# PSPS_AVNC_MITCH_2021-0_PRODUCTION.net
KiCad netlist of a schematic drawn in EAGLE
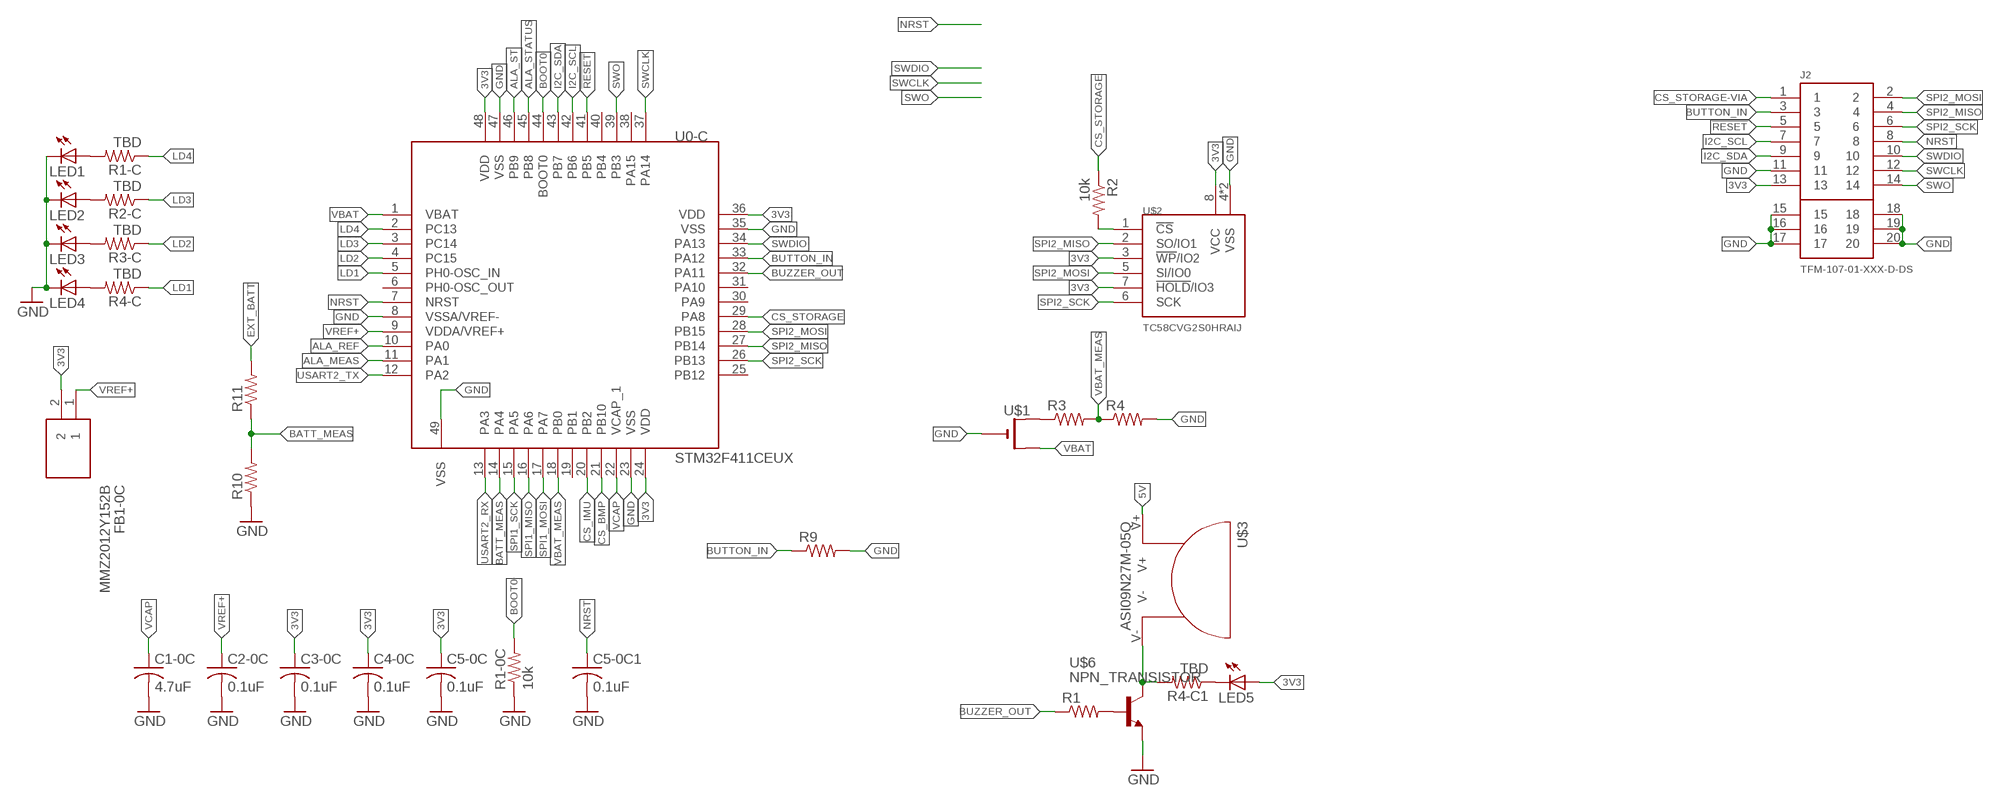
[diagram p0: schematic, sheet 1]
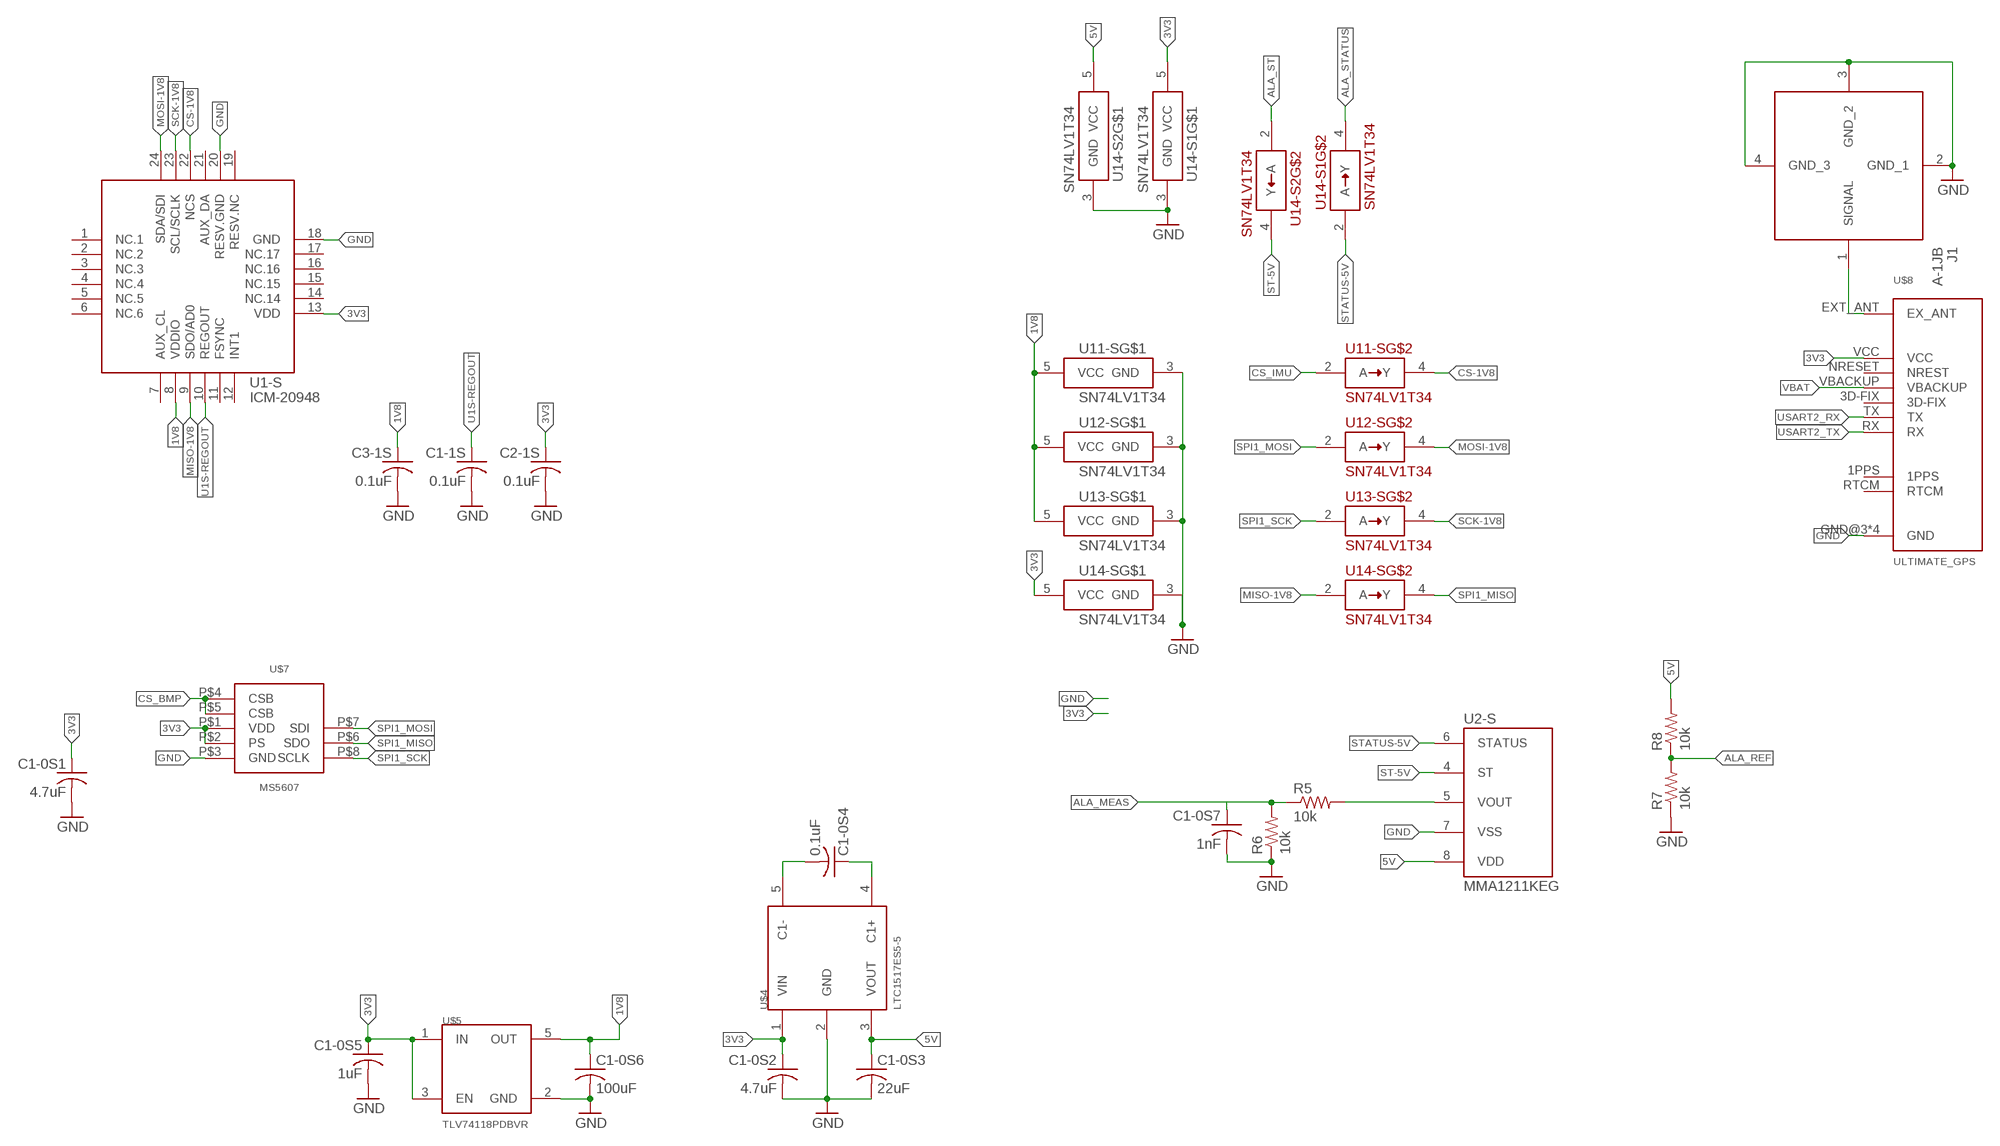
[diagram p1: schematic, sheet 2]

(export (version "E")
  (design (tool "Eeschema 10.0.6"))
  (components
    (comp (ref "C1-0C")
      (value "4.7uF")
      (footprint "eagle-import:C0805")
      (libsource (lib "eagle-import") (part "C-USC0805"))
    )
    (comp (ref "C2-0C")
      (value "0.1uF")
      (footprint "eagle-import:C0805")
      (libsource (lib "eagle-import") (part "C-USC0805"))
    )
    (comp (ref "C3-0C")
      (value "0.1uF")
      (footprint "eagle-import:C0805")
      (libsource (lib "eagle-import") (part "C-USC0805"))
    )
    (comp (ref "C4-0C")
      (value "0.1uF")
      (footprint "eagle-import:C0805")
      (libsource (lib "eagle-import") (part "C-USC0805"))
    )
    (comp (ref "C5-0C")
      (value "0.1uF")
      (footprint "eagle-import:C0805")
      (libsource (lib "eagle-import") (part "C-USC0805"))
    )
    (comp (ref "C5-0C1")
      (value "0.1uF")
      (footprint "eagle-import:C0805")
      (libsource (lib "eagle-import") (part "C-USC0805"))
    )
    (comp (ref "FB1-0C")
      (value "MMZ2012Y152B")
      (footprint "eagle-import:BEADC2012X105N")
      (fields (field (name "MOUSER_PART_NUMBER") "810-MMZ2012Y152B"))
      (libsource (lib "eagle-import") (part "MMZ2012Y152B"))
    )
    (comp (ref "J2")
      (value "TFM-107-01-XXX-D-DS")
      (footprint "eagle-import:TFM-107-01-XXX-D-DS")
      (libsource (lib "eagle-import") (part "TFM-107-01-XXX-D-DS"))
    )
    (comp (ref "LED1")
      (value "LEDCHIPLED_0805")
      (footprint "eagle-import:CHIPLED_0805")
      (libsource (lib "eagle-import") (part "LEDCHIPLED_0805"))
    )
    (comp (ref "LED2")
      (value "LEDCHIPLED_0805")
      (footprint "eagle-import:CHIPLED_0805")
      (libsource (lib "eagle-import") (part "LEDCHIPLED_0805"))
    )
    (comp (ref "LED3")
      (value "LEDCHIPLED_0805")
      (footprint "eagle-import:CHIPLED_0805")
      (libsource (lib "eagle-import") (part "LEDCHIPLED_0805"))
    )
    (comp (ref "LED4")
      (value "LEDCHIPLED_0805")
      (footprint "eagle-import:CHIPLED_0805")
      (libsource (lib "eagle-import") (part "LEDCHIPLED_0805"))
    )
    (comp (ref "LED5")
      (value "LEDCHIPLED_0805")
      (footprint "eagle-import:CHIPLED_0805")
      (libsource (lib "eagle-import") (part "LEDCHIPLED_0805"))
    )
    (comp (ref "R1")
      (value "R-US_R0805")
      (footprint "eagle-import:R0805")
      (libsource (lib "eagle-import") (part "R-US_R0805"))
    )
    (comp (ref "R1-0C")
      (value "10k")
      (footprint "eagle-import:R0805")
      (libsource (lib "eagle-import") (part "R-US_R0805"))
    )
    (comp (ref "R1-C")
      (value "TBD")
      (footprint "eagle-import:R0805")
      (libsource (lib "eagle-import") (part "R-US_R0805"))
    )
    (comp (ref "R2")
      (value "10k")
      (footprint "eagle-import:R0805")
      (libsource (lib "eagle-import") (part "R-US_R0805"))
    )
    (comp (ref "R2-C")
      (value "TBD")
      (footprint "eagle-import:R0805")
      (libsource (lib "eagle-import") (part "R-US_R0805"))
    )
    (comp (ref "R3")
      (value "R-US_R0805")
      (footprint "eagle-import:R0805")
      (libsource (lib "eagle-import") (part "R-US_R0805"))
    )
    (comp (ref "R3-C")
      (value "TBD")
      (footprint "eagle-import:R0805")
      (libsource (lib "eagle-import") (part "R-US_R0805"))
    )
    (comp (ref "R4")
      (value "R-US_R0805")
      (footprint "eagle-import:R0805")
      (libsource (lib "eagle-import") (part "R-US_R0805"))
    )
    (comp (ref "R4-C")
      (value "TBD")
      (footprint "eagle-import:R0805")
      (libsource (lib "eagle-import") (part "R-US_R0805"))
    )
    (comp (ref "R4-C1")
      (value "TBD")
      (footprint "eagle-import:R0805")
      (libsource (lib "eagle-import") (part "R-US_R0805"))
    )
    (comp (ref "R9")
      (value "R-US_R0805")
      (footprint "eagle-import:R0805")
      (libsource (lib "eagle-import") (part "R-US_R0805"))
    )
    (comp (ref "R10")
      (value "R-US_R0805")
      (footprint "eagle-import:R0805")
      (libsource (lib "eagle-import") (part "R-US_R0805"))
    )
    (comp (ref "R11")
      (value "R-US_R0805")
      (footprint "eagle-import:R0805")
      (libsource (lib "eagle-import") (part "R-US_R0805"))
    )
    (comp (ref "U$1")
      (value "CR1220SMT")
      (footprint "eagle-import:CR1220-SMD")
      (libsource (lib "eagle-import") (part "CR1220SMT"))
    )
    (comp (ref "U$2")
      (value "TC58CVG2S0HRAIJ")
      (footprint "eagle-import:SON127P800X600X80-9T350X440N")
      (libsource (lib "eagle-import") (part "TC58CVG2S0HRAIJ"))
    )
    (comp (ref "U$3")
      (value "ASI09N27M-05Q")
      (footprint "eagle-import:ASI09N27M-05Q")
      (libsource (lib "eagle-import") (part "ASI09N27M-05Q"))
    )
    (comp (ref "U$6")
      (value "NPN_TRANSISTOR")
      (footprint "eagle-import:SOT23")
      (libsource (lib "eagle-import") (part "NPN_TRANSISTOR"))
    )
    (comp (ref "U0-C")
      (value "STM32F411CEUX")
      (footprint "eagle-import:QFN50P700X700X50-49T560N")
      (libsource (lib "eagle-import") (part "STM32F411CEUX"))
    )
    (comp (ref "C1-0S1")
      (value "4.7uF")
      (footprint "eagle-import:C0805")
      (libsource (lib "eagle-import") (part "C-USC0805"))
    )
    (comp (ref "C1-0S2")
      (value "4.7uF")
      (footprint "eagle-import:C0805")
      (libsource (lib "eagle-import") (part "C-USC0805"))
    )
    (comp (ref "C1-0S3")
      (value "22uF")
      (footprint "eagle-import:C0805")
      (libsource (lib "eagle-import") (part "C-USC0805"))
    )
    (comp (ref "C1-0S4")
      (value "0.1uF")
      (footprint "eagle-import:C0805")
      (libsource (lib "eagle-import") (part "C-USC0805"))
    )
    (comp (ref "C1-0S5")
      (value "1uF")
      (footprint "eagle-import:C0805")
      (libsource (lib "eagle-import") (part "C-USC0805"))
    )
    (comp (ref "C1-0S6")
      (value "100uF")
      (footprint "eagle-import:C0805")
      (libsource (lib "eagle-import") (part "C-USC0805"))
    )
    (comp (ref "C1-0S7")
      (value "1nF")
      (footprint "eagle-import:C0805")
      (libsource (lib "eagle-import") (part "C-USC0805"))
    )
    (comp (ref "C1-1S")
      (value "0.1uF")
      (footprint "eagle-import:C0805")
      (libsource (lib "eagle-import") (part "C-USC0805"))
    )
    (comp (ref "C2-1S")
      (value "0.1uF")
      (footprint "eagle-import:C0805")
      (libsource (lib "eagle-import") (part "C-USC0805"))
    )
    (comp (ref "C3-1S")
      (value "0.1uF")
      (footprint "eagle-import:C0805")
      (libsource (lib "eagle-import") (part "C-USC0805"))
    )
    (comp (ref "J1")
      (value "A-1JB")
      (footprint "eagle-import:A1JB")
      (fields (field (name "MOUSER_PART_NUMBER") "523-A-1JB"))
      (libsource (lib "eagle-import") (part "A-1JB"))
    )
    (comp (ref "R5")
      (value "10k")
      (footprint "eagle-import:R0805")
      (libsource (lib "eagle-import") (part "R-US_R0805"))
    )
    (comp (ref "R6")
      (value "10k")
      (footprint "eagle-import:R0805")
      (libsource (lib "eagle-import") (part "R-US_R0805"))
    )
    (comp (ref "R7")
      (value "10k")
      (footprint "eagle-import:R0805")
      (libsource (lib "eagle-import") (part "R-US_R0805"))
    )
    (comp (ref "R8")
      (value "10k")
      (footprint "eagle-import:R0805")
      (libsource (lib "eagle-import") (part "R-US_R0805"))
    )
    (comp (ref "U$4")
      (value "LTC1517ES5-5")
      (footprint "eagle-import:SOT95P280X145-5N")
      (libsource (lib "eagle-import") (part "LTC1517ES5-5"))
    )
    (comp (ref "U$5")
      (value "TLV74118PDBVR")
      (footprint "eagle-import:SOT95P280X145-5N")
      (libsource (lib "eagle-import") (part "TLV74118PDBVR"))
    )
    (comp (ref "U$7")
      (value "MS5607")
      (footprint "eagle-import:MS5607")
      (libsource (lib "eagle-import") (part "MS5607"))
    )
    (comp (ref "U$8")
      (value "ULTIMATE_GPS")
      (footprint "eagle-import:FGPMMOPA6H")
      (libsource (lib "eagle-import") (part "ULTIMATE_GPS"))
    )
    (comp (ref "U1-S")
      (value "ICM-20948")
      (footprint "eagle-import:QFN40P300X300X105-25T159X175")
      (libsource (lib "eagle-import") (part "ICM-20948"))
    )
    (comp (ref "U2-S")
      (value "MMA1211KEG")
      (footprint "eagle-import:SOIC127P1041X355-16N")
      (libsource (lib "eagle-import") (part "MMA1211KEG"))
    )
    (comp (ref "U11-S")
      (value "SN74LV1T34")
      (footprint "eagle-import:SOT65P210X110-5")
      (libsource (lib "eagle-import") (part "SN74LV1T34"))
    )
    (comp (ref "U12-S")
      (value "SN74LV1T34")
      (footprint "eagle-import:SOT65P210X110-5")
      (libsource (lib "eagle-import") (part "SN74LV1T34"))
    )
    (comp (ref "U13-S")
      (value "SN74LV1T34")
      (footprint "eagle-import:SOT65P210X110-5")
      (libsource (lib "eagle-import") (part "SN74LV1T34"))
    )
    (comp (ref "U14-S")
      (value "SN74LV1T34")
      (footprint "eagle-import:SOT65P210X110-5")
      (libsource (lib "eagle-import") (part "SN74LV1T34"))
    )
    (comp (ref "U14-S1")
      (value "SN74LV1T34")
      (footprint "eagle-import:SOT65P210X110-5")
      (libsource (lib "eagle-import") (part "SN74LV1T34"))
    )
    (comp (ref "U14-S2")
      (value "SN74LV1T34")
      (footprint "eagle-import:SOT65P210X110-5")
      (libsource (lib "eagle-import") (part "SN74LV1T34"))
    )
  )
  (nets
    (net (code "1") (name "1V8") (class "Default")
      (node (ref "C1-0S6") (pin "1") (pinfunction "1_1") (pintype "passive"))
      (node (ref "C3-1S") (pin "1") (pinfunction "1_1") (pintype "passive"))
      (node (ref "U$5") (pin "5") (pinfunction "OUT_5") (pintype "bidirectional"))
      (node (ref "U1-S") (pin "8") (pinfunction "VDDIO_8") (pintype "bidirectional"))
      (node (ref "U11-S") (pin "5") (pinfunction "VCC_5") (pintype "bidirectional"))
      (node (ref "U12-S") (pin "5") (pinfunction "VCC_5") (pintype "bidirectional"))
      (node (ref "U13-S") (pin "5") (pinfunction "VCC_5") (pintype "bidirectional"))
    )
    (net (code "2") (name "3V3") (class "Default")
      (node (ref "C1-0S1") (pin "1") (pinfunction "1_1") (pintype "passive"))
      (node (ref "C1-0S2") (pin "1") (pinfunction "1_1") (pintype "passive"))
      (node (ref "C1-0S5") (pin "1") (pinfunction "1_1") (pintype "passive"))
      (node (ref "C2-1S") (pin "1") (pinfunction "1_1") (pintype "passive"))
      (node (ref "C3-0C") (pin "1") (pinfunction "1_1") (pintype "passive"))
      (node (ref "C4-0C") (pin "1") (pinfunction "1_1") (pintype "passive"))
      (node (ref "C5-0C") (pin "1") (pinfunction "1_1") (pintype "passive"))
      (node (ref "FB1-0C") (pin "2") (pinfunction "2_2") (pintype "bidirectional"))
      (node (ref "J2") (pin "13") (pinfunction "13_13") (pintype "bidirectional"))
      (node (ref "LED5") (pin "A") (pinfunction "A_A") (pintype "passive"))
      (node (ref "U$2") (pin "3") (pinfunction "~{WP}/IO2_3") (pintype "bidirectional"))
      (node (ref "U$2") (pin "7") (pinfunction "~{HOLD}/IO3_7") (pintype "bidirectional"))
      (node (ref "U$2") (pin "8") (pinfunction "VCC_8") (pintype "bidirectional"))
      (node (ref "U$4") (pin "1") (pinfunction "VIN_1") (pintype "bidirectional"))
      (node (ref "U$5") (pin "1") (pinfunction "IN_1") (pintype "bidirectional"))
      (node (ref "U$5") (pin "3") (pinfunction "EN_3") (pintype "bidirectional"))
      (node (ref "U$7") (pin "P$1") (pinfunction "VDD_P$1") (pintype "bidirectional"))
      (node (ref "U$7") (pin "P$2") (pinfunction "PS_P$2") (pintype "bidirectional"))
      (node (ref "U$8") (pin "VCC") (pinfunction "VCC_VCC") (pintype "bidirectional"))
      (node (ref "U0-C") (pin "24") (pinfunction "VDD_24") (pintype "bidirectional"))
      (node (ref "U0-C") (pin "36") (pinfunction "VDD_36") (pintype "bidirectional"))
      (node (ref "U0-C") (pin "48") (pinfunction "VDD_48") (pintype "bidirectional"))
      (node (ref "U1-S") (pin "13") (pinfunction "VDD_13") (pintype "bidirectional"))
      (node (ref "U14-S") (pin "5") (pinfunction "VCC_5") (pintype "bidirectional"))
      (node (ref "U14-S1") (pin "5") (pinfunction "VCC_5") (pintype "bidirectional"))
    )
    (net (code "3") (name "5V") (class "Default")
      (node (ref "C1-0S3") (pin "1") (pinfunction "1_1") (pintype "passive"))
      (node (ref "R8") (pin "2") (pinfunction "2_2") (pintype "passive"))
      (node (ref "U$3") (pin "V+") (pinfunction "V+_V+") (pintype "bidirectional"))
      (node (ref "U$4") (pin "3") (pinfunction "VOUT_3") (pintype "bidirectional"))
      (node (ref "U14-S2") (pin "5") (pinfunction "VCC_5") (pintype "bidirectional"))
      (node (ref "U2-S") (pin "8") (pinfunction "VDD_8") (pintype "bidirectional"))
    )
    (net (code "4") (name "ALA_MEAS") (class "Default")
      (node (ref "C1-0S7") (pin "1") (pinfunction "1_1") (pintype "passive"))
      (node (ref "R5") (pin "1") (pinfunction "1_1") (pintype "passive"))
      (node (ref "R6") (pin "2") (pinfunction "2_2") (pintype "passive"))
      (node (ref "U0-C") (pin "11") (pinfunction "PA1_11") (pintype "bidirectional"))
    )
    (net (code "5") (name "ALA_REF") (class "Default")
      (node (ref "R7") (pin "2") (pinfunction "2_2") (pintype "passive"))
      (node (ref "R8") (pin "1") (pinfunction "1_1") (pintype "passive"))
      (node (ref "U0-C") (pin "10") (pinfunction "PA0_10") (pintype "bidirectional"))
    )
    (net (code "6") (name "ALA_ST") (class "Default")
      (node (ref "U0-C") (pin "46") (pinfunction "PB9_46") (pintype "bidirectional"))
      (node (ref "U14-S2") (pin "2") (pinfunction "A_2") (pintype "bidirectional"))
    )
    (net (code "7") (name "ALA_STATUS") (class "Default")
      (node (ref "U0-C") (pin "45") (pinfunction "PB8_45") (pintype "bidirectional"))
      (node (ref "U14-S1") (pin "4") (pinfunction "Y_4") (pintype "bidirectional"))
    )
    (net (code "8") (name "BATT_MEAS") (class "Default")
      (node (ref "R10") (pin "2") (pinfunction "2_2") (pintype "passive"))
      (node (ref "R11") (pin "1") (pinfunction "1_1") (pintype "passive"))
      (node (ref "U0-C") (pin "14") (pinfunction "PA4_14") (pintype "bidirectional"))
    )
    (net (code "9") (name "BOOT0") (class "Default")
      (node (ref "R1-0C") (pin "2") (pinfunction "2_2") (pintype "passive"))
      (node (ref "U0-C") (pin "44") (pinfunction "BOOT0_44") (pintype "bidirectional"))
    )
    (net (code "10") (name "BUTTON_IN") (class "Default")
      (node (ref "J2") (pin "3") (pinfunction "3_3") (pintype "bidirectional"))
      (node (ref "R9") (pin "1") (pinfunction "1_1") (pintype "passive"))
      (node (ref "U0-C") (pin "33") (pinfunction "PA12_33") (pintype "bidirectional"))
    )
    (net (code "11") (name "BUZZER_OUT") (class "Default")
      (node (ref "R1") (pin "1") (pinfunction "1_1") (pintype "passive"))
      (node (ref "U0-C") (pin "32") (pinfunction "PA11_32") (pintype "bidirectional"))
    )
    (net (code "12") (name "CS-1V8") (class "Default")
      (node (ref "U1-S") (pin "22") (pinfunction "NCS_22") (pintype "bidirectional"))
      (node (ref "U11-S") (pin "4") (pinfunction "Y_4") (pintype "bidirectional"))
    )
    (net (code "13") (name "CS_BMP") (class "Default")
      (node (ref "U$7") (pin "P$4") (pinfunction "CSB_P$4") (pintype "bidirectional"))
      (node (ref "U$7") (pin "P$5") (pinfunction "CSB_P$5") (pintype "bidirectional"))
      (node (ref "U0-C") (pin "21") (pinfunction "PB10_21") (pintype "bidirectional"))
    )
    (net (code "14") (name "CS_IMU") (class "Default")
      (node (ref "U0-C") (pin "20") (pinfunction "PB2_20") (pintype "bidirectional"))
      (node (ref "U11-S") (pin "2") (pinfunction "A_2") (pintype "bidirectional"))
    )
    (net (code "15") (name "CS_STORAGE") (class "Default")
      (node (ref "R2") (pin "1") (pinfunction "1_1") (pintype "passive"))
      (node (ref "U0-C") (pin "29") (pinfunction "PA8_29") (pintype "bidirectional"))
    )
    (net (code "16") (name "CS_STORAGE-VIA") (class "Default")
      (node (ref "J2") (pin "1") (pinfunction "1_1") (pintype "bidirectional"))
      (node (ref "R2") (pin "2") (pinfunction "2_2") (pintype "passive"))
      (node (ref "U$2") (pin "1") (pinfunction "~{CS}_1") (pintype "bidirectional"))
    )
    (net (code "17") (name "EXT_BATT") (class "Default")
      (node (ref "R11") (pin "2") (pinfunction "2_2") (pintype "passive"))
    )
    (net (code "18") (name "GND") (class "Default")
      (node (ref "C1-0C") (pin "2") (pinfunction "2_2") (pintype "passive"))
      (node (ref "C1-0S1") (pin "2") (pinfunction "2_2") (pintype "passive"))
      (node (ref "C1-0S2") (pin "2") (pinfunction "2_2") (pintype "passive"))
      (node (ref "C1-0S3") (pin "2") (pinfunction "2_2") (pintype "passive"))
      (node (ref "C1-0S5") (pin "2") (pinfunction "2_2") (pintype "passive"))
      (node (ref "C1-0S6") (pin "2") (pinfunction "2_2") (pintype "passive"))
      (node (ref "C1-0S7") (pin "2") (pinfunction "2_2") (pintype "passive"))
      (node (ref "C1-1S") (pin "2") (pinfunction "2_2") (pintype "passive"))
      (node (ref "C2-0C") (pin "2") (pinfunction "2_2") (pintype "passive"))
      (node (ref "C2-1S") (pin "2") (pinfunction "2_2") (pintype "passive"))
      (node (ref "C3-0C") (pin "2") (pinfunction "2_2") (pintype "passive"))
      (node (ref "C3-1S") (pin "2") (pinfunction "2_2") (pintype "passive"))
      (node (ref "C4-0C") (pin "2") (pinfunction "2_2") (pintype "passive"))
      (node (ref "C5-0C") (pin "2") (pinfunction "2_2") (pintype "passive"))
      (node (ref "C5-0C1") (pin "2") (pinfunction "2_2") (pintype "passive"))
      (node (ref "J1") (pin "2") (pinfunction "GND_1_2") (pintype "bidirectional"))
      (node (ref "J1") (pin "3") (pinfunction "GND_2_3") (pintype "bidirectional"))
      (node (ref "J1") (pin "4") (pinfunction "GND_3_4") (pintype "bidirectional"))
      (node (ref "J2") (pin "11") (pinfunction "11_11") (pintype "bidirectional"))
      (node (ref "J2") (pin "15") (pinfunction "15_15") (pintype "bidirectional"))
      (node (ref "J2") (pin "16") (pinfunction "16_16") (pintype "bidirectional"))
      (node (ref "J2") (pin "17") (pinfunction "17_17") (pintype "bidirectional"))
      (node (ref "J2") (pin "18") (pinfunction "18_18") (pintype "bidirectional"))
      (node (ref "J2") (pin "19") (pinfunction "19_19") (pintype "bidirectional"))
      (node (ref "J2") (pin "20") (pinfunction "20_20") (pintype "bidirectional"))
      (node (ref "LED1") (pin "C") (pinfunction "C_C") (pintype "passive"))
      (node (ref "LED2") (pin "C") (pinfunction "C_C") (pintype "passive"))
      (node (ref "LED3") (pin "C") (pinfunction "C_C") (pintype "passive"))
      (node (ref "LED4") (pin "C") (pinfunction "C_C") (pintype "passive"))
      (node (ref "R1-0C") (pin "1") (pinfunction "1_1") (pintype "passive"))
      (node (ref "R10") (pin "1") (pinfunction "1_1") (pintype "passive"))
      (node (ref "R4") (pin "2") (pinfunction "2_2") (pintype "passive"))
      (node (ref "R6") (pin "1") (pinfunction "1_1") (pintype "passive"))
      (node (ref "R7") (pin "1") (pinfunction "1_1") (pintype "passive"))
      (node (ref "R9") (pin "2") (pinfunction "2_2") (pintype "passive"))
      (node (ref "U$1") (pin "-") (pinfunction "-_-") (pintype "passive"))
      (node (ref "U$2") (pin "4") (pinfunction "VSS_4") (pintype "bidirectional"))
      (node (ref "U$2") (pin "9") (pinfunction "VSS_9") (pintype "bidirectional"))
      (node (ref "U$4") (pin "2") (pinfunction "GND_2") (pintype "bidirectional"))
      (node (ref "U$5") (pin "2") (pinfunction "GND_2") (pintype "bidirectional"))
      (node (ref "U$6") (pin "3") (pinfunction "E_3") (pintype "passive"))
      (node (ref "U$7") (pin "P$3") (pinfunction "GND_P$3") (pintype "bidirectional"))
      (node (ref "U$8") (pin "GND@12") (pinfunction "GND_GND@12") (pintype "bidirectional"))
      (node (ref "U$8") (pin "GND@19") (pinfunction "GND_GND@19") (pintype "bidirectional"))
      (node (ref "U$8") (pin "GND@3") (pinfunction "GND_GND@3") (pintype "bidirectional"))
      (node (ref "U$8") (pin "GND@8") (pinfunction "GND_GND@8") (pintype "bidirectional"))
      (node (ref "U0-C") (pin "23") (pinfunction "VSS_23") (pintype "bidirectional"))
      (node (ref "U0-C") (pin "35") (pinfunction "VSS_35") (pintype "bidirectional"))
      (node (ref "U0-C") (pin "47") (pinfunction "VSS_47") (pintype "bidirectional"))
      (node (ref "U0-C") (pin "49") (pinfunction "VSS_49") (pintype "bidirectional"))
      (node (ref "U0-C") (pin "8") (pinfunction "VSSA/VREF-_8") (pintype "bidirectional"))
      (node (ref "U1-S") (pin "18") (pinfunction "GND_18") (pintype "bidirectional"))
      (node (ref "U1-S") (pin "20") (pinfunction "RESV.GND_20") (pintype "bidirectional"))
      (node (ref "U11-S") (pin "3") (pinfunction "GND_3") (pintype "bidirectional"))
      (node (ref "U12-S") (pin "3") (pinfunction "GND_3") (pintype "bidirectional"))
      (node (ref "U13-S") (pin "3") (pinfunction "GND_3") (pintype "bidirectional"))
      (node (ref "U14-S") (pin "3") (pinfunction "GND_3") (pintype "bidirectional"))
      (node (ref "U14-S1") (pin "3") (pinfunction "GND_3") (pintype "bidirectional"))
      (node (ref "U14-S2") (pin "3") (pinfunction "GND_3") (pintype "bidirectional"))
      (node (ref "U2-S") (pin "7") (pinfunction "VSS_7") (pintype "bidirectional"))
    )
    (net (code "19") (name "I2C_SCL") (class "Default")
      (node (ref "J2") (pin "7") (pinfunction "7_7") (pintype "bidirectional"))
      (node (ref "U0-C") (pin "42") (pinfunction "PB6_42") (pintype "bidirectional"))
    )
    (net (code "20") (name "I2C_SDA") (class "Default")
      (node (ref "J2") (pin "9") (pinfunction "9_9") (pintype "bidirectional"))
      (node (ref "U0-C") (pin "43") (pinfunction "PB7_43") (pintype "bidirectional"))
    )
    (net (code "21") (name "LD1") (class "Default")
      (node (ref "R4-C") (pin "1") (pinfunction "1_1") (pintype "passive"))
      (node (ref "U0-C") (pin "5") (pinfunction "PH0-OSC_IN_5") (pintype "bidirectional"))
    )
    (net (code "22") (name "LD2") (class "Default")
      (node (ref "R3-C") (pin "1") (pinfunction "1_1") (pintype "passive"))
      (node (ref "U0-C") (pin "4") (pinfunction "PC15_4") (pintype "bidirectional"))
    )
    (net (code "23") (name "LD3") (class "Default")
      (node (ref "R2-C") (pin "1") (pinfunction "1_1") (pintype "passive"))
      (node (ref "U0-C") (pin "3") (pinfunction "PC14_3") (pintype "bidirectional"))
    )
    (net (code "24") (name "LD4") (class "Default")
      (node (ref "R1-C") (pin "1") (pinfunction "1_1") (pintype "passive"))
      (node (ref "U0-C") (pin "2") (pinfunction "PC13_2") (pintype "bidirectional"))
    )
    (net (code "25") (name "MISO-1V8") (class "Default")
      (node (ref "U1-S") (pin "9") (pinfunction "SDO/AD0_9") (pintype "bidirectional"))
      (node (ref "U14-S") (pin "2") (pinfunction "A_2") (pintype "bidirectional"))
    )
    (net (code "26") (name "MOSI-1V8") (class "Default")
      (node (ref "U1-S") (pin "24") (pinfunction "SDA/SDI_24") (pintype "bidirectional"))
      (node (ref "U12-S") (pin "4") (pinfunction "Y_4") (pintype "bidirectional"))
    )
    (net (code "27") (name "NRST") (class "Default")
      (node (ref "C5-0C1") (pin "1") (pinfunction "1_1") (pintype "passive"))
      (node (ref "J2") (pin "8") (pinfunction "8_8") (pintype "bidirectional"))
      (node (ref "U0-C") (pin "7") (pinfunction "NRST_7") (pintype "bidirectional"))
    )
    (net (code "28") (name "Net-(J1-SIGNAL)") (class "Default")
      (node (ref "J1") (pin "1") (pinfunction "SIGNAL_1") (pintype "bidirectional"))
      (node (ref "U$8") (pin "EXT_ANT") (pinfunction "EX_ANT_EXT_ANT") (pintype "bidirectional"))
    )
    (net (code "29") (name "Net-(LED1-PadA)") (class "Default")
      (node (ref "LED1") (pin "A") (pinfunction "A_A") (pintype "passive"))
      (node (ref "R1-C") (pin "2") (pinfunction "2_2") (pintype "passive"))
    )
    (net (code "30") (name "Net-(LED2-PadA)") (class "Default")
      (node (ref "LED2") (pin "A") (pinfunction "A_A") (pintype "passive"))
      (node (ref "R2-C") (pin "2") (pinfunction "2_2") (pintype "passive"))
    )
    (net (code "31") (name "Net-(LED3-PadA)") (class "Default")
      (node (ref "LED3") (pin "A") (pinfunction "A_A") (pintype "passive"))
      (node (ref "R3-C") (pin "2") (pinfunction "2_2") (pintype "passive"))
    )
    (net (code "32") (name "Net-(LED4-PadA)") (class "Default")
      (node (ref "LED4") (pin "A") (pinfunction "A_A") (pintype "passive"))
      (node (ref "R4-C") (pin "2") (pinfunction "2_2") (pintype "passive"))
    )
    (net (code "33") (name "Net-(LED5-PadC)") (class "Default")
      (node (ref "LED5") (pin "C") (pinfunction "C_C") (pintype "passive"))
      (node (ref "R4-C1") (pin "1") (pinfunction "1_1") (pintype "passive"))
    )
    (net (code "34") (name "Net-(U$1-+)") (class "Default")
      (node (ref "R3") (pin "1") (pinfunction "1_1") (pintype "passive"))
      (node (ref "U$1") (pin "+$1") (pinfunction "+_+$1") (pintype "passive"))
    )
    (net (code "35") (name "Net-(U$4-C1+)") (class "Default")
      (node (ref "C1-0S4") (pin "1") (pinfunction "1_1") (pintype "passive"))
      (node (ref "U$4") (pin "4") (pinfunction "C1+_4") (pintype "bidirectional"))
    )
    (net (code "36") (name "Net-(U$4-C1-)") (class "Default")
      (node (ref "C1-0S4") (pin "2") (pinfunction "2_2") (pintype "passive"))
      (node (ref "U$4") (pin "5") (pinfunction "C1-_5") (pintype "bidirectional"))
    )
    (net (code "37") (name "Net-(U$6-B)") (class "Default")
      (node (ref "R1") (pin "2") (pinfunction "2_2") (pintype "passive"))
      (node (ref "U$6") (pin "1") (pinfunction "B_1") (pintype "passive"))
    )
    (net (code "38") (name "Net-(U$6-C)") (class "Default")
      (node (ref "R4-C1") (pin "2") (pinfunction "2_2") (pintype "passive"))
      (node (ref "U$3") (pin "V-") (pinfunction "V-_V-") (pintype "bidirectional"))
      (node (ref "U$6") (pin "2") (pinfunction "C_2") (pintype "passive"))
    )
    (net (code "39") (name "Net-(U2-S-VOUT)") (class "Default")
      (node (ref "R5") (pin "2") (pinfunction "2_2") (pintype "passive"))
      (node (ref "U2-S") (pin "5") (pinfunction "VOUT_5") (pintype "bidirectional"))
    )
    (net (code "40") (name "SCK-1V8") (class "Default")
      (node (ref "U1-S") (pin "23") (pinfunction "SCL/SCLK_23") (pintype "bidirectional"))
      (node (ref "U13-S") (pin "4") (pinfunction "Y_4") (pintype "bidirectional"))
    )
    (net (code "41") (name "SPI1_MISO") (class "Default")
      (node (ref "U$7") (pin "P$6") (pinfunction "SDO_P$6") (pintype "bidirectional"))
      (node (ref "U0-C") (pin "16") (pinfunction "PA6_16") (pintype "bidirectional"))
      (node (ref "U14-S") (pin "4") (pinfunction "Y_4") (pintype "bidirectional"))
    )
    (net (code "42") (name "SPI1_MOSI") (class "Default")
      (node (ref "U$7") (pin "P$7") (pinfunction "SDI_P$7") (pintype "bidirectional"))
      (node (ref "U0-C") (pin "17") (pinfunction "PA7_17") (pintype "bidirectional"))
      (node (ref "U12-S") (pin "2") (pinfunction "A_2") (pintype "bidirectional"))
    )
    (net (code "43") (name "SPI1_SCK") (class "Default")
      (node (ref "U$7") (pin "P$8") (pinfunction "SCLK_P$8") (pintype "bidirectional"))
      (node (ref "U0-C") (pin "15") (pinfunction "PA5_15") (pintype "bidirectional"))
      (node (ref "U13-S") (pin "2") (pinfunction "A_2") (pintype "bidirectional"))
    )
    (net (code "44") (name "SPI2_MISO") (class "Default")
      (node (ref "J2") (pin "4") (pinfunction "4_4") (pintype "bidirectional"))
      (node (ref "U$2") (pin "2") (pinfunction "SO/IO1_2") (pintype "bidirectional"))
      (node (ref "U0-C") (pin "27") (pinfunction "PB14_27") (pintype "bidirectional"))
    )
    (net (code "45") (name "SPI2_MOSI") (class "Default")
      (node (ref "J2") (pin "2") (pinfunction "2_2") (pintype "bidirectional"))
      (node (ref "U$2") (pin "5") (pinfunction "SI/IO0_5") (pintype "bidirectional"))
      (node (ref "U0-C") (pin "28") (pinfunction "PB15_28") (pintype "bidirectional"))
    )
    (net (code "46") (name "SPI2_SCK") (class "Default")
      (node (ref "J2") (pin "6") (pinfunction "6_6") (pintype "bidirectional"))
      (node (ref "U$2") (pin "6") (pinfunction "SCK_6") (pintype "bidirectional"))
      (node (ref "U0-C") (pin "26") (pinfunction "PB13_26") (pintype "bidirectional"))
    )
    (net (code "47") (name "ST-5V") (class "Default")
      (node (ref "U14-S2") (pin "4") (pinfunction "Y_4") (pintype "bidirectional"))
      (node (ref "U2-S") (pin "4") (pinfunction "ST_4") (pintype "bidirectional"))
    )
    (net (code "48") (name "STATUS-5V") (class "Default")
      (node (ref "U14-S1") (pin "2") (pinfunction "A_2") (pintype "bidirectional"))
      (node (ref "U2-S") (pin "6") (pinfunction "STATUS_6") (pintype "bidirectional"))
    )
    (net (code "49") (name "SWCLK") (class "Default")
      (node (ref "J2") (pin "12") (pinfunction "12_12") (pintype "bidirectional"))
      (node (ref "U0-C") (pin "37") (pinfunction "PA14_37") (pintype "bidirectional"))
    )
    (net (code "50") (name "SWDIO") (class "Default")
      (node (ref "J2") (pin "10") (pinfunction "10_10") (pintype "bidirectional"))
      (node (ref "U0-C") (pin "34") (pinfunction "PA13_34") (pintype "bidirectional"))
    )
    (net (code "51") (name "SWO") (class "Default")
      (node (ref "J2") (pin "14") (pinfunction "14_14") (pintype "bidirectional"))
      (node (ref "U0-C") (pin "39") (pinfunction "PB3_39") (pintype "bidirectional"))
    )
    (net (code "52") (name "U1S-REGOUT") (class "Default")
      (node (ref "C1-1S") (pin "1") (pinfunction "1_1") (pintype "passive"))
      (node (ref "U1-S") (pin "10") (pinfunction "REGOUT_10") (pintype "bidirectional"))
    )
    (net (code "53") (name "USART2_RX") (class "Default")
      (node (ref "U$8") (pin "TX") (pinfunction "TX_TX") (pintype "bidirectional"))
      (node (ref "U0-C") (pin "13") (pinfunction "PA3_13") (pintype "bidirectional"))
    )
    (net (code "54") (name "USART2_TX") (class "Default")
      (node (ref "U$8") (pin "RX") (pinfunction "RX_RX") (pintype "bidirectional"))
      (node (ref "U0-C") (pin "12") (pinfunction "PA2_12") (pintype "bidirectional"))
    )
    (net (code "55") (name "VBAT") (class "Default")
      (node (ref "U$1") (pin "+$2") (pinfunction "+1_+$2") (pintype "passive"))
      (node (ref "U$8") (pin "VBACKUP") (pinfunction "VBACKUP_VBACKUP") (pintype "bidirectional"))
      (node (ref "U0-C") (pin "1") (pinfunction "VBAT_1") (pintype "bidirectional"))
    )
    (net (code "56") (name "VBAT_MEAS") (class "Default")
      (node (ref "R3") (pin "2") (pinfunction "2_2") (pintype "passive"))
      (node (ref "R4") (pin "1") (pinfunction "1_1") (pintype "passive"))
      (node (ref "U0-C") (pin "18") (pinfunction "PB0_18") (pintype "bidirectional"))
    )
    (net (code "57") (name "VCAP") (class "Default")
      (node (ref "C1-0C") (pin "1") (pinfunction "1_1") (pintype "passive"))
      (node (ref "U0-C") (pin "22") (pinfunction "VCAP_1_22") (pintype "bidirectional"))
    )
    (net (code "58") (name "VREF+") (class "Default")
      (node (ref "C2-0C") (pin "1") (pinfunction "1_1") (pintype "passive"))
      (node (ref "FB1-0C") (pin "1") (pinfunction "1_1") (pintype "bidirectional"))
      (node (ref "U0-C") (pin "9") (pinfunction "VDDA/VREF+_9") (pintype "bidirectional"))
    )
    (net (code "59") (name "unconnected-(U$8-NREST-PadNRESET)") (class "Default")
      (node (ref "U$8") (pin "NRESET") (pinfunction "NREST_NRESET") (pintype "bidirectional"))
    )
    (net (code "60") (name "unconnected-(U$8-Pad1PPS)") (class "Default")
      (node (ref "U$8") (pin "1PPS") (pinfunction "1PPS_1PPS") (pintype "bidirectional"))
    )
    (net (code "61") (name "unconnected-(U$8-Pad3D-FIX)") (class "Default")
      (node (ref "U$8") (pin "3D-FIX") (pinfunction "3D-FIX_3D-FIX") (pintype "bidirectional"))
    )
    (net (code "62") (name "unconnected-(U$8-PadRTCM)") (class "Default")
      (node (ref "U$8") (pin "RTCM") (pinfunction "RTCM_RTCM") (pintype "bidirectional"))
    )
    (net (code "63") (name "unconnected-(U0-C-PA9-Pad30)") (class "Default")
      (node (ref "U0-C") (pin "30") (pinfunction "PA9_30") (pintype "bidirectional"))
    )
    (net (code "64") (name "unconnected-(U0-C-PA10-Pad31)") (class "Default")
      (node (ref "U0-C") (pin "31") (pinfunction "PA10_31") (pintype "bidirectional"))
    )
    (net (code "65") (name "unconnected-(U0-C-PA15-Pad38)") (class "Default")
      (node (ref "U0-C") (pin "38") (pinfunction "PA15_38") (pintype "bidirectional"))
    )
    (net (code "66") (name "unconnected-(U0-C-PB1-Pad19)") (class "Default")
      (node (ref "U0-C") (pin "19") (pinfunction "PB1_19") (pintype "bidirectional"))
    )
    (net (code "67") (name "unconnected-(U0-C-PB4-Pad40)") (class "Default")
      (node (ref "U0-C") (pin "40") (pinfunction "PB4_40") (pintype "bidirectional"))
    )
    (net (code "68") (name "unconnected-(U0-C-PB12-Pad25)") (class "Default")
      (node (ref "U0-C") (pin "25") (pinfunction "PB12_25") (pintype "bidirectional"))
    )
    (net (code "69") (name "unconnected-(U0-C-PH0-OSC_OUT-Pad6)") (class "Default")
      (node (ref "U0-C") (pin "6") (pinfunction "PH0-OSC_OUT_6") (pintype "bidirectional"))
    )
    (net (code "70") (name "unconnected-(U1-S-AUX_CL-Pad7)") (class "Default")
      (node (ref "U1-S") (pin "7") (pinfunction "AUX_CL_7") (pintype "bidirectional"))
    )
    (net (code "71") (name "unconnected-(U1-S-AUX_DA-Pad21)") (class "Default")
      (node (ref "U1-S") (pin "21") (pinfunction "AUX_DA_21") (pintype "bidirectional"))
    )
    (net (code "72") (name "unconnected-(U1-S-FSYNC-Pad11)") (class "Default")
      (node (ref "U1-S") (pin "11") (pinfunction "FSYNC_11") (pintype "bidirectional"))
    )
    (net (code "73") (name "unconnected-(U1-S-INT1-Pad12)") (class "Default")
      (node (ref "U1-S") (pin "12") (pinfunction "INT1_12") (pintype "bidirectional"))
    )
    (net (code "74") (name "unconnected-(U1-S-NC.1-Pad1)") (class "Default")
      (node (ref "U1-S") (pin "1") (pinfunction "NC.1_1") (pintype "bidirectional"))
    )
    (net (code "75") (name "unconnected-(U1-S-NC.2-Pad2)") (class "Default")
      (node (ref "U1-S") (pin "2") (pinfunction "NC.2_2") (pintype "bidirectional"))
    )
    (net (code "76") (name "unconnected-(U1-S-NC.3-Pad3)") (class "Default")
      (node (ref "U1-S") (pin "3") (pinfunction "NC.3_3") (pintype "bidirectional"))
    )
    (net (code "77") (name "unconnected-(U1-S-NC.4-Pad4)") (class "Default")
      (node (ref "U1-S") (pin "4") (pinfunction "NC.4_4") (pintype "bidirectional"))
    )
    (net (code "78") (name "unconnected-(U1-S-NC.5-Pad5)") (class "Default")
      (node (ref "U1-S") (pin "5") (pinfunction "NC.5_5") (pintype "bidirectional"))
    )
    (net (code "79") (name "unconnected-(U1-S-NC.6-Pad6)") (class "Default")
      (node (ref "U1-S") (pin "6") (pinfunction "NC.6_6") (pintype "bidirectional"))
    )
    (net (code "80") (name "unconnected-(U1-S-NC.14-Pad14)") (class "Default")
      (node (ref "U1-S") (pin "14") (pinfunction "NC.14_14") (pintype "bidirectional"))
    )
    (net (code "81") (name "unconnected-(U1-S-NC.15-Pad15)") (class "Default")
      (node (ref "U1-S") (pin "15") (pinfunction "NC.15_15") (pintype "bidirectional"))
    )
    (net (code "82") (name "unconnected-(U1-S-NC.16-Pad16)") (class "Default")
      (node (ref "U1-S") (pin "16") (pinfunction "NC.16_16") (pintype "bidirectional"))
    )
    (net (code "83") (name "unconnected-(U1-S-NC.17-Pad17)") (class "Default")
      (node (ref "U1-S") (pin "17") (pinfunction "NC.17_17") (pintype "bidirectional"))
    )
    (net (code "84") (name "unconnected-(U1-S-RESV.NC-Pad19)") (class "Default")
      (node (ref "U1-S") (pin "19") (pinfunction "RESV.NC_19") (pintype "bidirectional"))
    )
    (net (code "85") (name "~{RESET}") (class "Default")
      (node (ref "J2") (pin "5") (pinfunction "5_5") (pintype "bidirectional"))
      (node (ref "U0-C") (pin "41") (pinfunction "PB5_41") (pintype "bidirectional"))
    )
  )
)
